# Sheet1.net
KiCad netlist of a schematic drawn in Altium Designer
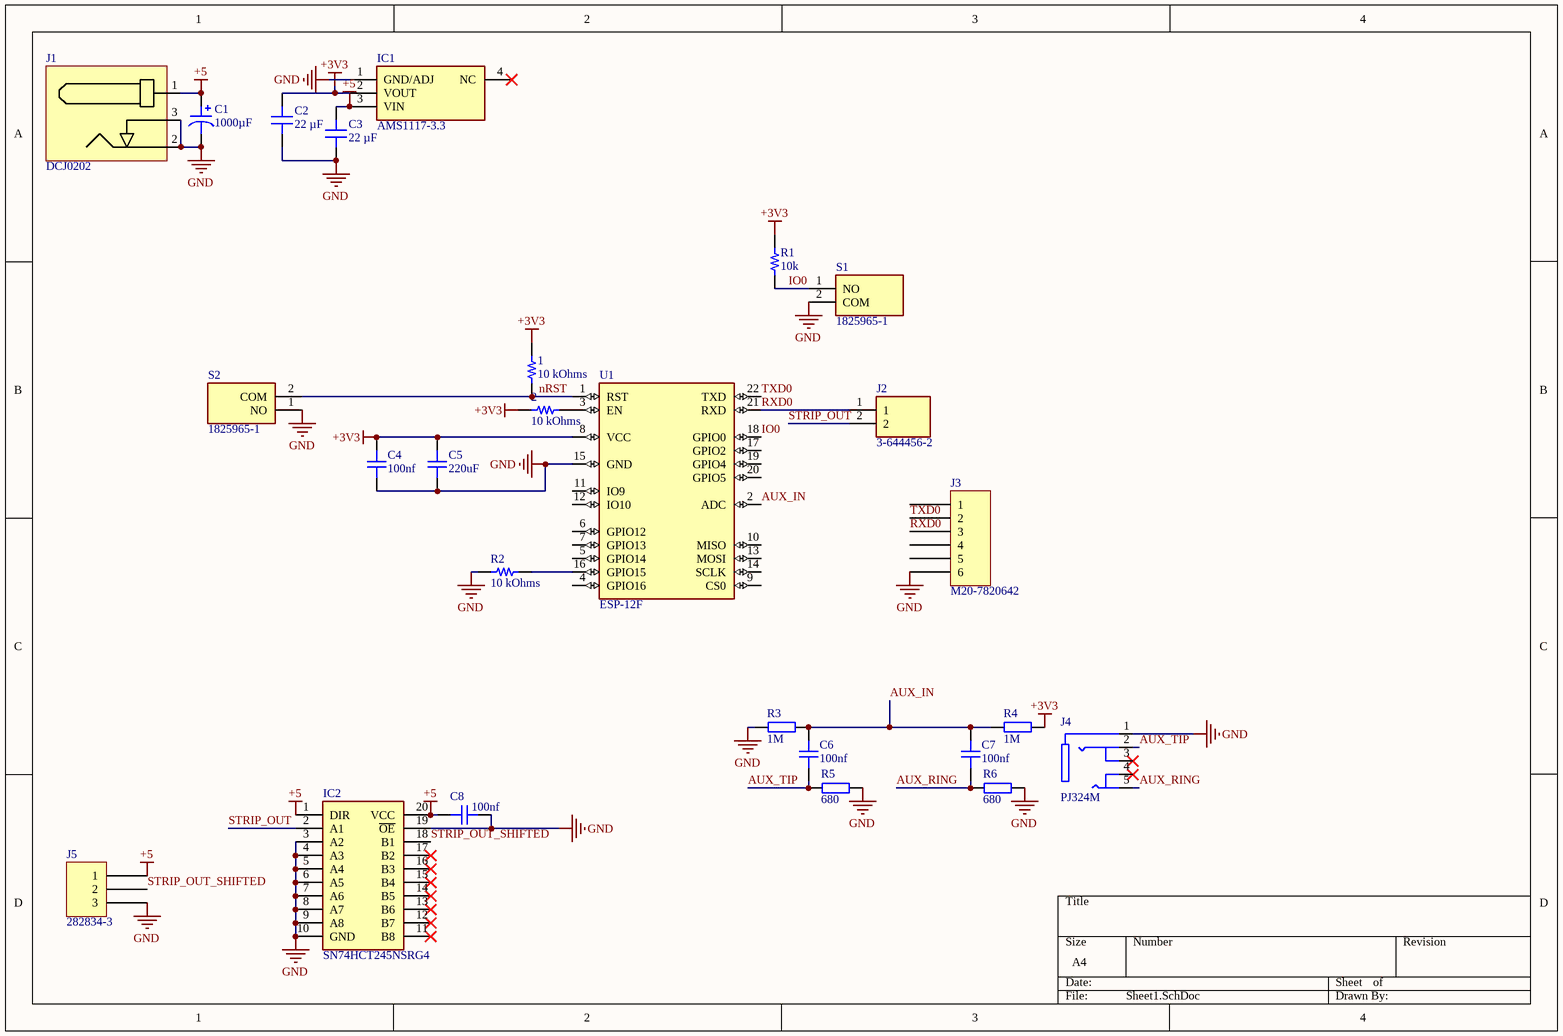
[diagram p0: Sheet1.SchDoc]

(export (version "E")
  (design (tool "Eeschema 10.0.6"))
  (components
    (comp (ref "1")
      (value "10 kOhms")
      (footprint "RES 0805_2012")
      (description "RES 10K OHM 0.1% 1/5W 0805")
      (fields
        (field (name "PART NUMBER") "9-2176375-1")
        (field (name "MANUFACTURER") "TE Connectivity Passive Product")
      )
      (libsource (lib "Celestial Altium Library - altium_library") (part "Resistor"))
    )
    (comp (ref "2")
      (value "10 kOhms")
      (footprint "RES 0805_2012")
      (description "RES 10K OHM 0.1% 1/5W 0805")
      (fields
        (field (name "PART NUMBER") "9-2176375-1")
        (field (name "MANUFACTURER") "TE Connectivity Passive Product")
      )
      (libsource (lib "Celestial Altium Library - altium_library") (part "Resistor"))
    )
    (comp (ref "C1")
      (value "1000µF")
      (footprint "CAP TH ALUM ELEC D8.00mm S3.50mm H17.50mm")
      (description "CAP ALUM 1000UF 20% 6.3V RADIAL")
      (fields (field (name "PART NUMBER") "6.3YXG1000MEFC8X16") (field (name "MANUFACTURER") "Rubycon"))
      (libsource (lib "Celestial Altium Library - altium_library") (part "Polarised Capacitor"))
    )
    (comp (ref "C2")
      (value "22 µF")
      (footprint "CAP 0805_2012")
      (description "CAP CER 22UF 6.3V X5R 0805")
      (fields
        (field (name "PART NUMBER") "0805X226M6R3CT")
        (field (name "MANUFACTURER") "Walsin Technology Corporation")
      )
      (libsource (lib "Celestial Altium Library - altium_library") (part "Capacitor"))
    )
    (comp (ref "C3")
      (value "22 µF")
      (footprint "CAP 0805_2012")
      (description "CAP CER 22UF 6.3V X5R 0805")
      (fields
        (field (name "PART NUMBER") "0805X226M6R3CT")
        (field (name "MANUFACTURER") "Walsin Technology Corporation")
      )
      (libsource (lib "Celestial Altium Library - altium_library") (part "Capacitor"))
    )
    (comp (ref "C4")
      (value "100nf")
      (footprint "CAP_0805")
      (description "Capacitor SMD 0805 6V3")
      (libsource (lib "Schematic-Lib-PhilsLab") (part "CAP_0805_6V3"))
    )
    (comp (ref "C5")
      (value "220uF")
      (footprint "CAP_0805")
      (description "Capacitor SMD 0805 6V3")
      (libsource (lib "Schematic-Lib-PhilsLab") (part "CAP_0805_6V3"))
    )
    (comp (ref "C6")
      (value "100nf")
      (footprint "CAP_0805")
      (description "Capacitor SMD 0805 6V3")
      (libsource (lib "Schematic-Lib-PhilsLab") (part "CAP_0805_6V3"))
    )
    (comp (ref "C7")
      (value "100nf")
      (footprint "CAP_0805")
      (description "Capacitor SMD 0805 6V3")
      (libsource (lib "Schematic-Lib-PhilsLab") (part "CAP_0805_6V3"))
    )
    (comp (ref "C8")
      (value "100nf")
      (footprint "CAP_0805")
      (description "Capacitor SMD 0805 6V3")
      (libsource (lib "Schematic-Lib-PhilsLab") (part "CAP_0805_6V3"))
    )
    (comp (ref "IC1")
      (value "AMS1117-3.3")
      (footprint "SamacSys:SOT229P700X180-4N")
      (description "Integrated Circuit")
      (libsource (lib "SamacSys") (part "AMS1117-3.3"))
    )
    (comp (ref "IC2")
      (value "SN74HCT245NSRG4")
      (footprint "SamacSys:SOIC127P780X200-20N")
      (description "Integrated Circuit")
      (fields (field (name "MOUSER PART NUMBER") "595-SN74HCT245NSRG4"))
      (libsource (lib "*") (part "SN74HCT245NSRG4"))
    )
    (comp (ref "J1")
      (value "DCJ0202")
      (footprint "DCJ0202")
      (description "DC Barrell Jack 2.1mm 24V 5A THT")
      (fields (field (name "MANUFACTURER") "CONEC"))
      (libsource (lib "Schematic-Lib-PhilsLab") (part "DCJ0202"))
    )
    (comp (ref "J2")
      (value "3-644456-2")
      (footprint "TE_3-644456-2")
      (fields (field (name "MF") "{'manufacturer': u'TE Connectivity'}"))
      (libsource (lib "3-644456-2") (part "3-644456-2"))
    )
    (comp (ref "J3")
      (value "M20-7820642")
      (footprint "HARWIN M20-7820645")
      (description "CONN RCPT 6POS 0.1 GOLD PCB")
      (fields (field (name "MANUFACTURER") "Harwin Inc."))
      (libsource (lib "Celestial Altium Library - altium_library") (part "6 Pin"))
    )
    (comp (ref "J4")
      (value "PJ324M")
      (footprint "WENZHOU_PJ324M:WENZHOU_PJ324M")
      (description "Headphone Stereo jack/Audio connector")
      (fields (field (name "MF") "Wenzhou QingPu Electronics Co.Ltd"))
      (libsource (lib "PJ324M") (part "PJ324M"))
    )
    (comp (ref "J5")
      (value "282834-3")
      (footprint "TE 282834-3")
      (description "TERM BLK 3P SIDE ENT 2.54MM PCB")
      (fields (field (name "MANUFACTURER") "TE Connectivity AMP Connectors") (field (name "VOLTAGE") "150V"))
      (libsource (lib "Celestial Altium Library - altium_library") (part "3 Pin"))
    )
    (comp (ref "R1")
      (value "10k")
      (footprint "RES 0805_2012")
      (description "RES 10K OHM 0.1% 1/5W 0805")
      (fields
        (field (name "PART NUMBER") "9-2176375-1")
        (field (name "MANUFACTURER") "TE Connectivity Passive Product")
      )
      (libsource (lib "Celestial Altium Library - altium_library") (part "Resistor"))
    )
    (comp (ref "R2")
      (value "10 kOhms")
      (footprint "RES 0805_2012")
      (description "RES 10K OHM 0.1% 1/5W 0805")
      (fields
        (field (name "PART NUMBER") "9-2176375-1")
        (field (name "MANUFACTURER") "TE Connectivity Passive Product")
      )
      (libsource (lib "Celestial Altium Library - altium_library") (part "Resistor"))
    )
    (comp (ref "R3")
      (value "1M")
      (footprint "RES_0805")
      (description "Resistor SMD 0805")
      (libsource (lib "Schematic-Lib-PhilsLab") (part "RES_0805"))
    )
    (comp (ref "R4")
      (value "1M")
      (footprint "RES_0805")
      (description "Resistor SMD 0805")
      (libsource (lib "Schematic-Lib-PhilsLab") (part "RES_0805"))
    )
    (comp (ref "R5")
      (value "680")
      (footprint "RES_0805")
      (description "Resistor SMD 0805")
      (libsource (lib "Schematic-Lib-PhilsLab") (part "RES_0805"))
    )
    (comp (ref "R6")
      (value "680")
      (footprint "RES_0805")
      (description "Resistor SMD 0805")
      (libsource (lib "Schematic-Lib-PhilsLab") (part "RES_0805"))
    )
    (comp (ref "S1")
      (value "1825965-1")
      (footprint "SamacSys:18259651")
      (description "Switch")
      (libsource (lib "SamacSys") (part "1825965-1"))
    )
    (comp (ref "S2")
      (value "1825965-1")
      (footprint "SamacSys:18259651")
      (description "Switch")
      (libsource (lib "") (part "1825965-1_1"))
    )
    (comp (ref "U1")
      (value "ESP-12F")
      (footprint "ESP-12F:ESP-12F")
      (description "WiFi Module")
      (fields (field (name "MF") "AI-Thinker"))
      (libsource (lib "ESP-12F") (part "ESP-12F"))
    )
  )
  (nets
    (net (code "1") (name "+3V3") (class "Default")
      (node (ref "1") (pin "1") (pinfunction "1_1") (pintype "passive"))
      (node (ref "2") (pin "1") (pinfunction "1_1") (pintype "passive"))
      (node (ref "C2") (pin "2") (pinfunction "2_2") (pintype "passive"))
      (node (ref "C4") (pin "1") (pinfunction "1_1") (pintype "passive"))
      (node (ref "C5") (pin "1") (pinfunction "1_1") (pintype "passive"))
      (node (ref "IC1") (pin "2") (pinfunction "VOUT_2") (pintype "passive"))
      (node (ref "R1") (pin "2") (pinfunction "2_2") (pintype "passive"))
      (node (ref "R4") (pin "1") (pinfunction "1_1") (pintype "passive"))
      (node (ref "U1") (pin "8") (pinfunction "VCC_8") (pintype "bidirectional"))
    )
    (net (code "2") (name "+5") (class "Default")
      (node (ref "C1") (pin "1") (pinfunction "1_1") (pintype "passive"))
      (node (ref "C3") (pin "2") (pinfunction "2_2") (pintype "passive"))
      (node (ref "C8") (pin "2") (pinfunction "2_2") (pintype "passive"))
      (node (ref "IC1") (pin "3") (pinfunction "VIN_3") (pintype "passive"))
      (node (ref "IC2") (pin "1") (pinfunction "DIR_1") (pintype "passive"))
      (node (ref "IC2") (pin "20") (pinfunction "VCC_20") (pintype "passive"))
      (node (ref "J1") (pin "1") (pinfunction "1_1") (pintype "passive"))
      (node (ref "J5") (pin "1") (pinfunction "1_1") (pintype "passive"))
    )
    (net (code "3") (name "/AUX_IN") (class "Default")
      (node (ref "C6") (pin "2") (pinfunction "2_2") (pintype "passive"))
      (node (ref "C7") (pin "2") (pinfunction "2_2") (pintype "passive"))
      (node (ref "R3") (pin "1") (pinfunction "1_1") (pintype "passive"))
      (node (ref "R4") (pin "2") (pinfunction "2_2") (pintype "passive"))
      (node (ref "U1") (pin "2") (pinfunction "ADC_2") (pintype "bidirectional"))
    )
    (net (code "4") (name "/AUX_RING") (class "Default")
      (node (ref "C7") (pin "1") (pinfunction "1_1") (pintype "passive"))
      (node (ref "J4") (pin "5") (pinfunction "TIP_2_5") (pintype "passive"))
      (node (ref "R6") (pin "2") (pinfunction "2_2") (pintype "passive"))
    )
    (net (code "5") (name "/AUX_TIP") (class "Default")
      (node (ref "C6") (pin "1") (pinfunction "1_1") (pintype "passive"))
      (node (ref "J4") (pin "2") (pinfunction "RING_1_2") (pintype "passive"))
      (node (ref "R5") (pin "1") (pinfunction "1_1") (pintype "passive"))
    )
    (net (code "6") (name "/IO0") (class "Default")
      (node (ref "R1") (pin "1") (pinfunction "1_1") (pintype "passive"))
      (node (ref "S1") (pin "1") (pinfunction "NO_1") (pintype "passive"))
      (node (ref "U1") (pin "18") (pinfunction "GPIO0_18") (pintype "bidirectional"))
    )
    (net (code "7") (name "/RXD0") (class "Default")
      (node (ref "J2") (pin "1") (pinfunction "1_1") (pintype "passive"))
      (node (ref "J3") (pin "3") (pinfunction "3_3") (pintype "passive"))
      (node (ref "U1") (pin "21") (pinfunction "RXD_21") (pintype "bidirectional"))
    )
    (net (code "8") (name "/STRIP_OUT") (class "Default")
      (node (ref "IC2") (pin "2") (pinfunction "A1_2") (pintype "passive"))
      (node (ref "J2") (pin "2") (pinfunction "2_2") (pintype "passive"))
    )
    (net (code "9") (name "/STRIP_OUT_SHIFTED") (class "Default")
      (node (ref "IC2") (pin "18") (pinfunction "B1_18") (pintype "passive"))
      (node (ref "J5") (pin "2") (pinfunction "2_2") (pintype "passive"))
    )
    (net (code "10") (name "/TXD0") (class "Default")
      (node (ref "J3") (pin "2") (pinfunction "2_2") (pintype "passive"))
      (node (ref "U1") (pin "22") (pinfunction "TXD_22") (pintype "bidirectional"))
    )
    (net (code "11") (name "/nRST") (class "Default")
      (node (ref "1") (pin "2") (pinfunction "2_2") (pintype "passive"))
      (node (ref "S2") (pin "2") (pinfunction "COM_2") (pintype "passive"))
      (node (ref "U1") (pin "1") (pinfunction "RST_1") (pintype "bidirectional"))
    )
    (net (code "12") (name "GND") (class "Default")
      (node (ref "C1") (pin "2") (pinfunction "2_2") (pintype "passive"))
      (node (ref "C2") (pin "1") (pinfunction "1_1") (pintype "passive"))
      (node (ref "C3") (pin "1") (pinfunction "1_1") (pintype "passive"))
      (node (ref "C4") (pin "2") (pinfunction "2_2") (pintype "passive"))
      (node (ref "C5") (pin "2") (pinfunction "2_2") (pintype "passive"))
      (node (ref "C8") (pin "1") (pinfunction "1_1") (pintype "passive"))
      (node (ref "IC1") (pin "1") (pinfunction "GND/ADJ_1") (pintype "passive"))
      (node (ref "IC2") (pin "10") (pinfunction "GND_10") (pintype "passive"))
      (node (ref "IC2") (pin "19") (pinfunction "~{OE}_19") (pintype "passive"))
      (node (ref "IC2") (pin "3") (pinfunction "A2_3") (pintype "passive"))
      (node (ref "IC2") (pin "4") (pinfunction "A3_4") (pintype "passive"))
      (node (ref "IC2") (pin "5") (pinfunction "A4_5") (pintype "passive"))
      (node (ref "IC2") (pin "6") (pinfunction "A5_6") (pintype "passive"))
      (node (ref "IC2") (pin "7") (pinfunction "A6_7") (pintype "passive"))
      (node (ref "IC2") (pin "8") (pinfunction "A7_8") (pintype "passive"))
      (node (ref "IC2") (pin "9") (pinfunction "A8_9") (pintype "passive"))
      (node (ref "J1") (pin "2") (pinfunction "2_2") (pintype "passive"))
      (node (ref "J1") (pin "3") (pinfunction "3_3") (pintype "passive"))
      (node (ref "J3") (pin "6") (pinfunction "6_6") (pintype "passive"))
      (node (ref "J4") (pin "1") (pinfunction "SLEEVE_1") (pintype "passive"))
      (node (ref "J5") (pin "3") (pinfunction "3_3") (pintype "passive"))
      (node (ref "R2") (pin "1") (pinfunction "1_1") (pintype "passive"))
      (node (ref "R3") (pin "2") (pinfunction "2_2") (pintype "passive"))
      (node (ref "R5") (pin "2") (pinfunction "2_2") (pintype "passive"))
      (node (ref "R6") (pin "1") (pinfunction "1_1") (pintype "passive"))
      (node (ref "S1") (pin "2") (pinfunction "COM_2") (pintype "passive"))
      (node (ref "S2") (pin "1") (pinfunction "NO_1") (pintype "passive"))
      (node (ref "U1") (pin "15") (pinfunction "GND_15") (pintype "bidirectional"))
    )
    (net (code "13") (name "Net-(U1-EN)") (class "Default")
      (node (ref "2") (pin "2") (pinfunction "2_2") (pintype "passive"))
      (node (ref "U1") (pin "3") (pinfunction "EN_3") (pintype "bidirectional"))
    )
    (net (code "14") (name "Net-(U1-GPIO15)") (class "Default")
      (node (ref "R2") (pin "2") (pinfunction "2_2") (pintype "passive"))
      (node (ref "U1") (pin "16") (pinfunction "GPIO15_16") (pintype "bidirectional"))
    )
    (net (code "15") (name "unconnected-(IC1-NC-Pad4)") (class "Default")
      (node (ref "IC1") (pin "4") (pinfunction "NC_4") (pintype "passive+no_connect"))
    )
    (net (code "16") (name "unconnected-(IC2-B2-Pad17)") (class "Default")
      (node (ref "IC2") (pin "17") (pinfunction "B2_17") (pintype "passive+no_connect"))
    )
    (net (code "17") (name "unconnected-(IC2-B3-Pad16)") (class "Default")
      (node (ref "IC2") (pin "16") (pinfunction "B3_16") (pintype "passive+no_connect"))
    )
    (net (code "18") (name "unconnected-(IC2-B4-Pad15)") (class "Default")
      (node (ref "IC2") (pin "15") (pinfunction "B4_15") (pintype "passive+no_connect"))
    )
    (net (code "19") (name "unconnected-(IC2-B5-Pad14)") (class "Default")
      (node (ref "IC2") (pin "14") (pinfunction "B5_14") (pintype "passive+no_connect"))
    )
    (net (code "20") (name "unconnected-(IC2-B6-Pad13)") (class "Default")
      (node (ref "IC2") (pin "13") (pinfunction "B6_13") (pintype "passive+no_connect"))
    )
    (net (code "21") (name "unconnected-(IC2-B7-Pad12)") (class "Default")
      (node (ref "IC2") (pin "12") (pinfunction "B7_12") (pintype "passive+no_connect"))
    )
    (net (code "22") (name "unconnected-(IC2-B8-Pad11)") (class "Default")
      (node (ref "IC2") (pin "11") (pinfunction "B8_11") (pintype "passive+no_connect"))
    )
    (net (code "23") (name "unconnected-(J3-Pad1)") (class "Default")
      (node (ref "J3") (pin "1") (pinfunction "1_1") (pintype "passive"))
    )
    (net (code "24") (name "unconnected-(J3-Pad4)") (class "Default")
      (node (ref "J3") (pin "4") (pinfunction "4_4") (pintype "passive"))
    )
    (net (code "25") (name "unconnected-(J3-Pad5)") (class "Default")
      (node (ref "J3") (pin "5") (pinfunction "5_5") (pintype "passive"))
    )
    (net (code "26") (name "unconnected-(J4-RING_2-Pad3)") (class "Default")
      (node (ref "J4") (pin "3") (pinfunction "RING_2_3") (pintype "passive+no_connect"))
    )
    (net (code "27") (name "unconnected-(J4-TIP_1-Pad4)") (class "Default")
      (node (ref "J4") (pin "4") (pinfunction "TIP_1_4") (pintype "passive+no_connect"))
    )
    (net (code "28") (name "unconnected-(U1-CS0-Pad9)") (class "Default")
      (node (ref "U1") (pin "9") (pinfunction "CS0_9") (pintype "bidirectional"))
    )
    (net (code "29") (name "unconnected-(U1-GPIO2-Pad17)") (class "Default")
      (node (ref "U1") (pin "17") (pinfunction "GPIO2_17") (pintype "bidirectional"))
    )
    (net (code "30") (name "unconnected-(U1-GPIO4-Pad19)") (class "Default")
      (node (ref "U1") (pin "19") (pinfunction "GPIO4_19") (pintype "bidirectional"))
    )
    (net (code "31") (name "unconnected-(U1-GPIO5-Pad20)") (class "Default")
      (node (ref "U1") (pin "20") (pinfunction "GPIO5_20") (pintype "bidirectional"))
    )
    (net (code "32") (name "unconnected-(U1-GPIO12-Pad6)") (class "Default")
      (node (ref "U1") (pin "6") (pinfunction "GPIO12_6") (pintype "bidirectional"))
    )
    (net (code "33") (name "unconnected-(U1-GPIO13-Pad7)") (class "Default")
      (node (ref "U1") (pin "7") (pinfunction "GPIO13_7") (pintype "bidirectional"))
    )
    (net (code "34") (name "unconnected-(U1-GPIO14-Pad5)") (class "Default")
      (node (ref "U1") (pin "5") (pinfunction "GPIO14_5") (pintype "bidirectional"))
    )
    (net (code "35") (name "unconnected-(U1-GPIO16-Pad4)") (class "Default")
      (node (ref "U1") (pin "4") (pinfunction "GPIO16_4") (pintype "bidirectional"))
    )
    (net (code "36") (name "unconnected-(U1-IO9-Pad11)") (class "Default")
      (node (ref "U1") (pin "11") (pinfunction "IO9_11") (pintype "bidirectional"))
    )
    (net (code "37") (name "unconnected-(U1-IO10-Pad12)") (class "Default")
      (node (ref "U1") (pin "12") (pinfunction "IO10_12") (pintype "bidirectional"))
    )
    (net (code "38") (name "unconnected-(U1-MISO-Pad10)") (class "Default")
      (node (ref "U1") (pin "10") (pinfunction "MISO_10") (pintype "bidirectional"))
    )
    (net (code "39") (name "unconnected-(U1-MOSI-Pad13)") (class "Default")
      (node (ref "U1") (pin "13") (pinfunction "MOSI_13") (pintype "bidirectional"))
    )
    (net (code "40") (name "unconnected-(U1-SCLK-Pad14)") (class "Default")
      (node (ref "U1") (pin "14") (pinfunction "SCLK_14") (pintype "bidirectional"))
    )
  )
)
